# ProperFeatherwing.net
KiCad netlist of a schematic drawn in EAGLE
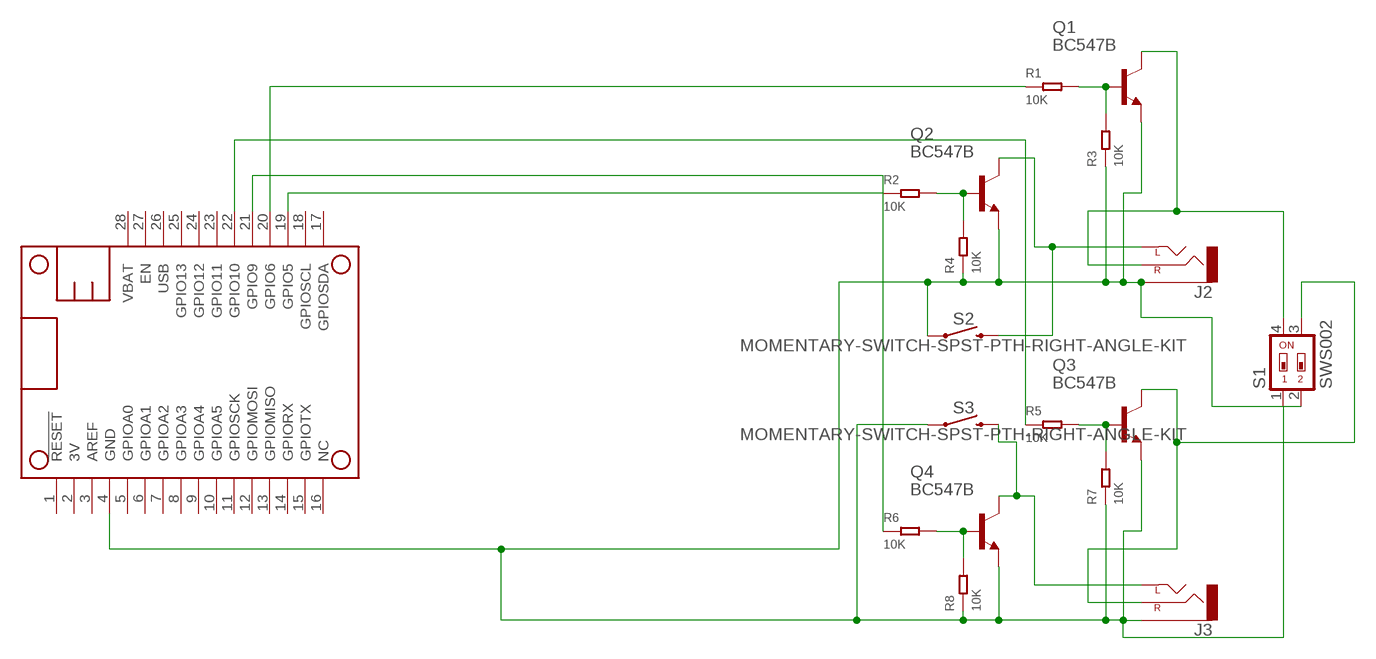
[diagram p0: schematic, sheet 1]

(export (version "E")
  (design (tool "Eeschema 10.0.6"))
  (components
    (comp (ref "J2")
      (value "AUDIO_JACK_2.5MM_2.5MM")
      (footprint "eagle-import:STEREOJACK2.5MM_STEREOJACK2.5MM")
      (libsource (lib "eagle-import") (part "AUDIO_JACK_2.5MM_2.5MM"))
    )
    (comp (ref "J3")
      (value "AUDIO_JACK_2.5MM_2.5MM")
      (footprint "eagle-import:STEREOJACK2.5MM_STEREOJACK2.5MM")
      (libsource (lib "eagle-import") (part "AUDIO_JACK_2.5MM_2.5MM"))
    )
    (comp (ref "MS2")
      (value "FEATHERWING")
      (footprint "eagle-import:FEATHERWING")
      (libsource (lib "eagle-import") (part "FEATHERWING"))
    )
    (comp (ref "Q1")
      (value "BC547B")
      (footprint "eagle-import:TO92")
      (libsource (lib "eagle-import") (part "BC547B"))
    )
    (comp (ref "Q2")
      (value "BC547B")
      (footprint "eagle-import:TO92")
      (libsource (lib "eagle-import") (part "BC547B"))
    )
    (comp (ref "Q3")
      (value "BC547B")
      (footprint "eagle-import:TO92")
      (libsource (lib "eagle-import") (part "BC547B"))
    )
    (comp (ref "Q4")
      (value "BC547B")
      (footprint "eagle-import:TO92")
      (libsource (lib "eagle-import") (part "BC547B"))
    )
    (comp (ref "R1")
      (value "10K")
      (footprint "eagle-import:PR-D2.3XL6.5MM")
      (fields (field (name "MPN") "FHCFR-1/4W-103J"))
      (libsource (lib "eagle-import") (part "DIP-RES-10K-5%-1/4W(PR-D2.3XL6.5MM)"))
    )
    (comp (ref "R2")
      (value "10K")
      (footprint "eagle-import:PR-D2.3XL6.5MM")
      (fields (field (name "MPN") "FHCFR-1/4W-103J"))
      (libsource (lib "eagle-import") (part "DIP-RES-10K-5%-1/4W(PR-D2.3XL6.5MM)"))
    )
    (comp (ref "R3")
      (value "10K")
      (footprint "eagle-import:PR-D2.3XL6.5MM")
      (fields (field (name "MPN") "FHCFR-1/4W-103J"))
      (libsource (lib "eagle-import") (part "DIP-RES-10K-5%-1/4W(PR-D2.3XL6.5MM)"))
    )
    (comp (ref "R4")
      (value "10K")
      (footprint "eagle-import:PR-D2.3XL6.5MM")
      (fields (field (name "MPN") "FHCFR-1/4W-103J"))
      (libsource (lib "eagle-import") (part "DIP-RES-10K-5%-1/4W(PR-D2.3XL6.5MM)"))
    )
    (comp (ref "R5")
      (value "10K")
      (footprint "eagle-import:PR-D2.3XL6.5MM")
      (fields (field (name "MPN") "FHCFR-1/4W-103J"))
      (libsource (lib "eagle-import") (part "DIP-RES-10K-5%-1/4W(PR-D2.3XL6.5MM)"))
    )
    (comp (ref "R6")
      (value "10K")
      (footprint "eagle-import:PR-D2.3XL6.5MM")
      (fields (field (name "MPN") "FHCFR-1/4W-103J"))
      (libsource (lib "eagle-import") (part "DIP-RES-10K-5%-1/4W(PR-D2.3XL6.5MM)"))
    )
    (comp (ref "R7")
      (value "10K")
      (footprint "eagle-import:PR-D2.3XL6.5MM")
      (fields (field (name "MPN") "FHCFR-1/4W-103J"))
      (libsource (lib "eagle-import") (part "DIP-RES-10K-5%-1/4W(PR-D2.3XL6.5MM)"))
    )
    (comp (ref "R8")
      (value "10K")
      (footprint "eagle-import:PR-D2.3XL6.5MM")
      (fields (field (name "MPN") "FHCFR-1/4W-103J"))
      (libsource (lib "eagle-import") (part "DIP-RES-10K-5%-1/4W(PR-D2.3XL6.5MM)"))
    )
    (comp (ref "S1")
      (value "SWS002")
      (footprint "eagle-import:SMS-002")
      (libsource (lib "eagle-import") (part "SWS002"))
    )
    (comp (ref "S2")
      (value "MOMENTARY-SWITCH-SPST-PTH-RIGHT-ANGLE-KIT")
      (footprint "eagle-import:TACTILE_SWITCH_PTH_RIGHT_ANGLE_KIT")
      (libsource (lib "eagle-import") (part "MOMENTARY-SWITCH-SPST-PTH-RIGHT-ANGLE-KIT"))
    )
    (comp (ref "S3")
      (value "MOMENTARY-SWITCH-SPST-PTH-RIGHT-ANGLE-KIT")
      (footprint "eagle-import:TACTILE_SWITCH_PTH_RIGHT_ANGLE_KIT")
      (libsource (lib "eagle-import") (part "MOMENTARY-SWITCH-SPST-PTH-RIGHT-ANGLE-KIT"))
    )
  )
  (nets
    (net (code "1") (name "/3V") (class "Default")
      (node (ref "MS2") (pin "2") (pinfunction "3V_2") (pintype "power_in"))
    )
    (net (code "2") (name "/USB") (class "Default")
      (node (ref "MS2") (pin "26") (pinfunction "USB_26") (pintype "power_in"))
    )
    (net (code "3") (name "/VBAT") (class "Default")
      (node (ref "MS2") (pin "28") (pinfunction "VBAT_28") (pintype "power_in"))
    )
    (net (code "4") (name "Net-(J2-LEFT)") (class "Default")
      (node (ref "J2") (pin "SHIELD") (pinfunction "LEFT_SHIELD") (pintype "bidirectional"))
      (node (ref "Q2") (pin "3") (pinfunction "C_3") (pintype "passive"))
      (node (ref "S2") (pin "2") (pinfunction "2_2") (pintype "passive"))
    )
    (net (code "5") (name "Net-(J2-RIGHT)") (class "Default")
      (node (ref "J2") (pin "TIP") (pinfunction "RIGHT_TIP") (pintype "bidirectional"))
      (node (ref "Q1") (pin "3") (pinfunction "C_3") (pintype "passive"))
      (node (ref "S1") (pin "4") (pinfunction "4_4") (pintype "passive"))
    )
    (net (code "6") (name "Net-(J2-SLEEVE)") (class "Default")
      (node (ref "J2") (pin "RING1") (pinfunction "SLEEVE_RING1") (pintype "bidirectional"))
      (node (ref "J3") (pin "RING1") (pinfunction "SLEEVE_RING1") (pintype "bidirectional"))
      (node (ref "MS2") (pin "4") (pinfunction "GND_4") (pintype "power_in"))
      (node (ref "Q1") (pin "1") (pinfunction "E_1") (pintype "passive"))
      (node (ref "Q2") (pin "1") (pinfunction "E_1") (pintype "passive"))
      (node (ref "Q3") (pin "1") (pinfunction "E_1") (pintype "passive"))
      (node (ref "Q4") (pin "1") (pinfunction "E_1") (pintype "passive"))
      (node (ref "R3") (pin "1") (pinfunction "1_1") (pintype "passive"))
      (node (ref "R4") (pin "1") (pinfunction "1_1") (pintype "passive"))
      (node (ref "R7") (pin "1") (pinfunction "1_1") (pintype "passive"))
      (node (ref "R8") (pin "1") (pinfunction "1_1") (pintype "passive"))
      (node (ref "S1") (pin "1") (pinfunction "1_1") (pintype "passive"))
      (node (ref "S1") (pin "2") (pinfunction "2_2") (pintype "passive"))
      (node (ref "S2") (pin "1") (pinfunction "1_1") (pintype "passive"))
      (node (ref "S3") (pin "1") (pinfunction "1_1") (pintype "passive"))
    )
    (net (code "7") (name "Net-(J3-LEFT)") (class "Default")
      (node (ref "J3") (pin "SHIELD") (pinfunction "LEFT_SHIELD") (pintype "bidirectional"))
      (node (ref "Q4") (pin "3") (pinfunction "C_3") (pintype "passive"))
      (node (ref "S3") (pin "2") (pinfunction "2_2") (pintype "passive"))
    )
    (net (code "8") (name "Net-(J3-RIGHT)") (class "Default")
      (node (ref "J3") (pin "TIP") (pinfunction "RIGHT_TIP") (pintype "bidirectional"))
      (node (ref "Q3") (pin "3") (pinfunction "C_3") (pintype "passive"))
      (node (ref "S1") (pin "3") (pinfunction "3_3") (pintype "passive"))
    )
    (net (code "9") (name "Net-(MS2-GPIO5)") (class "Default")
      (node (ref "MS2") (pin "19") (pinfunction "GPIO5_19") (pintype "bidirectional"))
      (node (ref "R2") (pin "1") (pinfunction "1_1") (pintype "passive"))
    )
    (net (code "10") (name "Net-(MS2-GPIO6)") (class "Default")
      (node (ref "MS2") (pin "20") (pinfunction "GPIO6_20") (pintype "bidirectional"))
      (node (ref "R1") (pin "1") (pinfunction "1_1") (pintype "passive"))
    )
    (net (code "11") (name "Net-(MS2-GPIO9)") (class "Default")
      (node (ref "MS2") (pin "21") (pinfunction "GPIO9_21") (pintype "bidirectional"))
      (node (ref "R6") (pin "1") (pinfunction "1_1") (pintype "passive"))
    )
    (net (code "12") (name "Net-(MS2-GPIO10)") (class "Default")
      (node (ref "MS2") (pin "22") (pinfunction "GPIO10_22") (pintype "bidirectional"))
      (node (ref "R5") (pin "1") (pinfunction "1_1") (pintype "passive"))
    )
    (net (code "13") (name "Net-(Q1-B)") (class "Default")
      (node (ref "Q1") (pin "2") (pinfunction "B_2") (pintype "passive"))
      (node (ref "R1") (pin "2") (pinfunction "2_2") (pintype "passive"))
      (node (ref "R3") (pin "2") (pinfunction "2_2") (pintype "passive"))
    )
    (net (code "14") (name "Net-(Q2-B)") (class "Default")
      (node (ref "Q2") (pin "2") (pinfunction "B_2") (pintype "passive"))
      (node (ref "R2") (pin "2") (pinfunction "2_2") (pintype "passive"))
      (node (ref "R4") (pin "2") (pinfunction "2_2") (pintype "passive"))
    )
    (net (code "15") (name "Net-(Q3-B)") (class "Default")
      (node (ref "Q3") (pin "2") (pinfunction "B_2") (pintype "passive"))
      (node (ref "R5") (pin "2") (pinfunction "2_2") (pintype "passive"))
      (node (ref "R7") (pin "2") (pinfunction "2_2") (pintype "passive"))
    )
    (net (code "16") (name "Net-(Q4-B)") (class "Default")
      (node (ref "Q4") (pin "2") (pinfunction "B_2") (pintype "passive"))
      (node (ref "R6") (pin "2") (pinfunction "2_2") (pintype "passive"))
      (node (ref "R8") (pin "2") (pinfunction "2_2") (pintype "passive"))
    )
    (net (code "17") (name "unconnected-(MS2-AREF-Pad3)") (class "Default")
      (node (ref "MS2") (pin "3") (pinfunction "AREF_3") (pintype "passive"))
    )
    (net (code "18") (name "unconnected-(MS2-EN-Pad27)") (class "Default")
      (node (ref "MS2") (pin "27") (pinfunction "EN_27") (pintype "passive"))
    )
    (net (code "19") (name "unconnected-(MS2-GPIO11-Pad23)") (class "Default")
      (node (ref "MS2") (pin "23") (pinfunction "GPIO11_23") (pintype "bidirectional"))
    )
    (net (code "20") (name "unconnected-(MS2-GPIO12-Pad24)") (class "Default")
      (node (ref "MS2") (pin "24") (pinfunction "GPIO12_24") (pintype "bidirectional"))
    )
    (net (code "21") (name "unconnected-(MS2-GPIO13-Pad25)") (class "Default")
      (node (ref "MS2") (pin "25") (pinfunction "GPIO13_25") (pintype "bidirectional"))
    )
    (net (code "22") (name "unconnected-(MS2-GPIOA0-Pad5)") (class "Default")
      (node (ref "MS2") (pin "5") (pinfunction "GPIOA0_5") (pintype "bidirectional"))
    )
    (net (code "23") (name "unconnected-(MS2-GPIOA1-Pad6)") (class "Default")
      (node (ref "MS2") (pin "6") (pinfunction "GPIOA1_6") (pintype "bidirectional"))
    )
    (net (code "24") (name "unconnected-(MS2-GPIOA2-Pad7)") (class "Default")
      (node (ref "MS2") (pin "7") (pinfunction "GPIOA2_7") (pintype "bidirectional"))
    )
    (net (code "25") (name "unconnected-(MS2-GPIOA3-Pad8)") (class "Default")
      (node (ref "MS2") (pin "8") (pinfunction "GPIOA3_8") (pintype "bidirectional"))
    )
    (net (code "26") (name "unconnected-(MS2-GPIOA4-Pad9)") (class "Default")
      (node (ref "MS2") (pin "9") (pinfunction "GPIOA4_9") (pintype "bidirectional"))
    )
    (net (code "27") (name "unconnected-(MS2-GPIOA5-Pad10)") (class "Default")
      (node (ref "MS2") (pin "10") (pinfunction "GPIOA5_10") (pintype "bidirectional"))
    )
    (net (code "28") (name "unconnected-(MS2-GPIOMISO-Pad13)") (class "Default")
      (node (ref "MS2") (pin "13") (pinfunction "GPIOMISO_13") (pintype "bidirectional"))
    )
    (net (code "29") (name "unconnected-(MS2-GPIOMOSI-Pad12)") (class "Default")
      (node (ref "MS2") (pin "12") (pinfunction "GPIOMOSI_12") (pintype "bidirectional"))
    )
    (net (code "30") (name "unconnected-(MS2-GPIORX-Pad14)") (class "Default")
      (node (ref "MS2") (pin "14") (pinfunction "GPIORX_14") (pintype "bidirectional"))
    )
    (net (code "31") (name "unconnected-(MS2-GPIOSCK-Pad11)") (class "Default")
      (node (ref "MS2") (pin "11") (pinfunction "GPIOSCK_11") (pintype "bidirectional"))
    )
    (net (code "32") (name "unconnected-(MS2-GPIOSCL-Pad18)") (class "Default")
      (node (ref "MS2") (pin "18") (pinfunction "GPIOSCL_18") (pintype "bidirectional"))
    )
    (net (code "33") (name "unconnected-(MS2-GPIOSDA-Pad17)") (class "Default")
      (node (ref "MS2") (pin "17") (pinfunction "GPIOSDA_17") (pintype "bidirectional"))
    )
    (net (code "34") (name "unconnected-(MS2-GPIOTX-Pad15)") (class "Default")
      (node (ref "MS2") (pin "15") (pinfunction "GPIOTX_15") (pintype "bidirectional"))
    )
    (net (code "35") (name "unconnected-(MS2-NC-Pad16)") (class "Default")
      (node (ref "MS2") (pin "16") (pinfunction "NC_16") (pintype "passive"))
    )
    (net (code "36") (name "unconnected-(MS2-~{RESET}-Pad1)") (class "Default")
      (node (ref "MS2") (pin "1") (pinfunction "~{RESET}_1") (pintype "input"))
    )
  )
)
